# PDN.net
KiCad netlist of a schematic drawn in Altium Designer
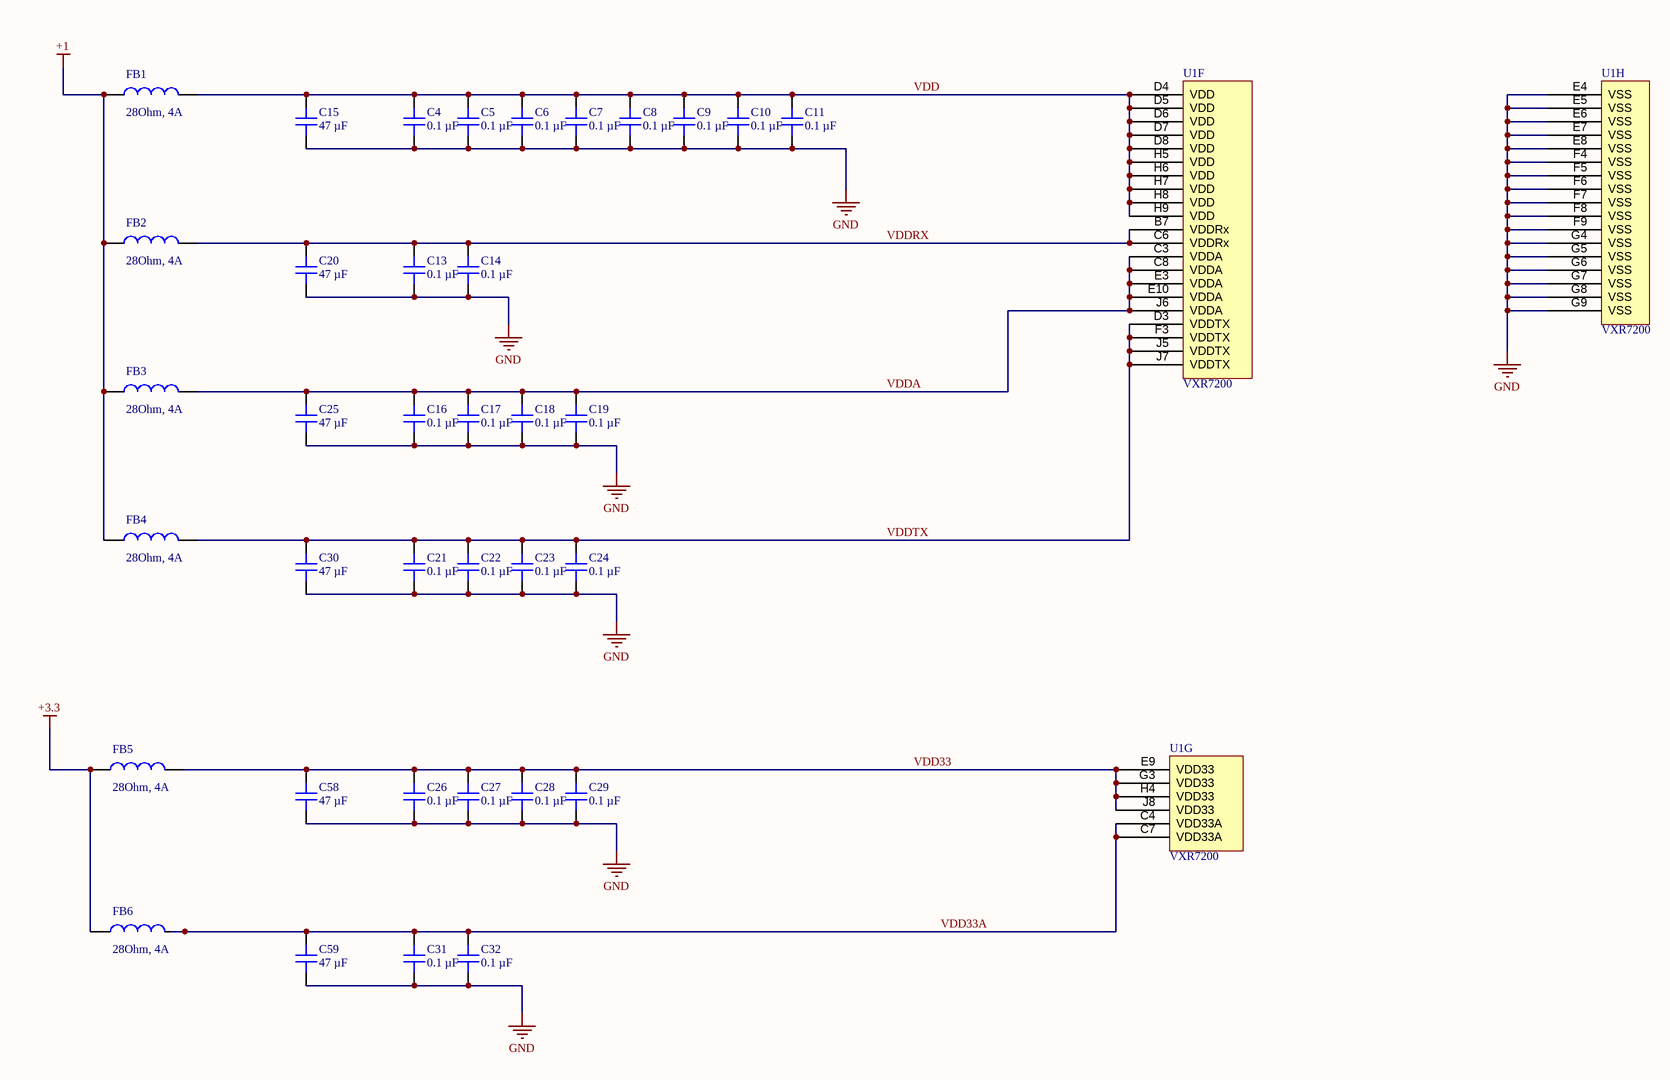
[diagram p0: PDN.SchDoc]

(export (version "E")
  (design (tool "Eeschema 10.0.6"))
  (components
    (comp (ref "C4")
      (value "0.1 µF")
      (footprint "CAP 0201_0603")
      (description "CAP CER 0.1UF 25V X5R 0201")
      (fields
        (field (name "PART NUMBER") "GRM033R61E104KE14D")
        (field (name "MANUFACTURER") "Murata Electronics")
      )
      (libsource (lib "Celestial Altium Library - altium_library") (part "Capacitor"))
    )
    (comp (ref "C5")
      (value "0.1 µF")
      (footprint "CAP 0201_0603")
      (description "CAP CER 0.1UF 25V X5R 0201")
      (fields
        (field (name "PART NUMBER") "GRM033R61E104KE14D")
        (field (name "MANUFACTURER") "Murata Electronics")
      )
      (libsource (lib "Celestial Altium Library - altium_library") (part "Capacitor"))
    )
    (comp (ref "C6")
      (value "0.1 µF")
      (footprint "CAP 0201_0603")
      (description "CAP CER 0.1UF 25V X5R 0201")
      (fields
        (field (name "PART NUMBER") "GRM033R61E104KE14D")
        (field (name "MANUFACTURER") "Murata Electronics")
      )
      (libsource (lib "Celestial Altium Library - altium_library") (part "Capacitor"))
    )
    (comp (ref "C7")
      (value "0.1 µF")
      (footprint "CAP 0201_0603")
      (description "CAP CER 0.1UF 25V X5R 0201")
      (fields
        (field (name "PART NUMBER") "GRM033R61E104KE14D")
        (field (name "MANUFACTURER") "Murata Electronics")
      )
      (libsource (lib "Celestial Altium Library - altium_library") (part "Capacitor"))
    )
    (comp (ref "C8")
      (value "0.1 µF")
      (footprint "CAP 0201_0603")
      (description "CAP CER 0.1UF 25V X5R 0201")
      (fields
        (field (name "PART NUMBER") "GRM033R61E104KE14D")
        (field (name "MANUFACTURER") "Murata Electronics")
      )
      (libsource (lib "Celestial Altium Library - altium_library") (part "Capacitor"))
    )
    (comp (ref "C9")
      (value "0.1 µF")
      (footprint "CAP 0201_0603")
      (description "CAP CER 0.1UF 25V X5R 0201")
      (fields
        (field (name "PART NUMBER") "GRM033R61E104KE14D")
        (field (name "MANUFACTURER") "Murata Electronics")
      )
      (libsource (lib "Celestial Altium Library - altium_library") (part "Capacitor"))
    )
    (comp (ref "C10")
      (value "0.1 µF")
      (footprint "CAP 0201_0603")
      (description "CAP CER 0.1UF 25V X5R 0201")
      (fields
        (field (name "PART NUMBER") "GRM033R61E104KE14D")
        (field (name "MANUFACTURER") "Murata Electronics")
      )
      (libsource (lib "Celestial Altium Library - altium_library") (part "Capacitor"))
    )
    (comp (ref "C11")
      (value "0.1 µF")
      (footprint "CAP 0201_0603")
      (description "CAP CER 0.1UF 25V X5R 0201")
      (fields
        (field (name "PART NUMBER") "GRM033R61E104KE14D")
        (field (name "MANUFACTURER") "Murata Electronics")
      )
      (libsource (lib "Celestial Altium Library - altium_library") (part "Capacitor"))
    )
    (comp (ref "C13")
      (value "0.1 µF")
      (footprint "CAP 0201_0603")
      (description "CAP CER 0.1UF 25V X5R 0201")
      (fields
        (field (name "PART NUMBER") "GRM033R61E104KE14D")
        (field (name "MANUFACTURER") "Murata Electronics")
      )
      (libsource (lib "Celestial Altium Library - altium_library") (part "Capacitor"))
    )
    (comp (ref "C14")
      (value "0.1 µF")
      (footprint "CAP 0201_0603")
      (description "CAP CER 0.1UF 25V X5R 0201")
      (fields
        (field (name "PART NUMBER") "GRM033R61E104KE14D")
        (field (name "MANUFACTURER") "Murata Electronics")
      )
      (libsource (lib "Celestial Altium Library - altium_library") (part "Capacitor"))
    )
    (comp (ref "C15")
      (value "47 µF")
      (footprint "CAP 0603_1608")
      (description "CAP CER 47UF 6.3V X5R 0603")
      (fields
        (field (name "PART NUMBER") "GRM188R60J476ME01D")
        (field (name "MANUFACTURER") "Murata Electronics")
      )
      (libsource (lib "Celestial Altium Library - altium_library") (part "Capacitor"))
    )
    (comp (ref "C16")
      (value "0.1 µF")
      (footprint "CAP 0201_0603")
      (description "CAP CER 0.1UF 25V X5R 0201")
      (fields
        (field (name "PART NUMBER") "GRM033R61E104KE14D")
        (field (name "MANUFACTURER") "Murata Electronics")
      )
      (libsource (lib "Celestial Altium Library - altium_library") (part "Capacitor"))
    )
    (comp (ref "C17")
      (value "0.1 µF")
      (footprint "CAP 0201_0603")
      (description "CAP CER 0.1UF 25V X5R 0201")
      (fields
        (field (name "PART NUMBER") "GRM033R61E104KE14D")
        (field (name "MANUFACTURER") "Murata Electronics")
      )
      (libsource (lib "Celestial Altium Library - altium_library") (part "Capacitor"))
    )
    (comp (ref "C18")
      (value "0.1 µF")
      (footprint "CAP 0201_0603")
      (description "CAP CER 0.1UF 25V X5R 0201")
      (fields
        (field (name "PART NUMBER") "GRM033R61E104KE14D")
        (field (name "MANUFACTURER") "Murata Electronics")
      )
      (libsource (lib "Celestial Altium Library - altium_library") (part "Capacitor"))
    )
    (comp (ref "C19")
      (value "0.1 µF")
      (footprint "CAP 0201_0603")
      (description "CAP CER 0.1UF 25V X5R 0201")
      (fields
        (field (name "PART NUMBER") "GRM033R61E104KE14D")
        (field (name "MANUFACTURER") "Murata Electronics")
      )
      (libsource (lib "Celestial Altium Library - altium_library") (part "Capacitor"))
    )
    (comp (ref "C20")
      (value "47 µF")
      (footprint "CAP 0603_1608")
      (description "CAP CER 47UF 6.3V X5R 0603")
      (fields
        (field (name "PART NUMBER") "GRM188R60J476ME01D")
        (field (name "MANUFACTURER") "Murata Electronics")
      )
      (libsource (lib "Celestial Altium Library - altium_library") (part "Capacitor"))
    )
    (comp (ref "C21")
      (value "0.1 µF")
      (footprint "CAP 0201_0603")
      (description "CAP CER 0.1UF 25V X5R 0201")
      (fields
        (field (name "PART NUMBER") "GRM033R61E104KE14D")
        (field (name "MANUFACTURER") "Murata Electronics")
      )
      (libsource (lib "Celestial Altium Library - altium_library") (part "Capacitor"))
    )
    (comp (ref "C22")
      (value "0.1 µF")
      (footprint "CAP 0201_0603")
      (description "CAP CER 0.1UF 25V X5R 0201")
      (fields
        (field (name "PART NUMBER") "GRM033R61E104KE14D")
        (field (name "MANUFACTURER") "Murata Electronics")
      )
      (libsource (lib "Celestial Altium Library - altium_library") (part "Capacitor"))
    )
    (comp (ref "C23")
      (value "0.1 µF")
      (footprint "CAP 0201_0603")
      (description "CAP CER 0.1UF 25V X5R 0201")
      (fields
        (field (name "PART NUMBER") "GRM033R61E104KE14D")
        (field (name "MANUFACTURER") "Murata Electronics")
      )
      (libsource (lib "Celestial Altium Library - altium_library") (part "Capacitor"))
    )
    (comp (ref "C24")
      (value "0.1 µF")
      (footprint "CAP 0201_0603")
      (description "CAP CER 0.1UF 25V X5R 0201")
      (fields
        (field (name "PART NUMBER") "GRM033R61E104KE14D")
        (field (name "MANUFACTURER") "Murata Electronics")
      )
      (libsource (lib "Celestial Altium Library - altium_library") (part "Capacitor"))
    )
    (comp (ref "C25")
      (value "47 µF")
      (footprint "CAP 0603_1608")
      (description "CAP CER 47UF 6.3V X5R 0603")
      (fields
        (field (name "PART NUMBER") "GRM188R60J476ME01D")
        (field (name "MANUFACTURER") "Murata Electronics")
      )
      (libsource (lib "Celestial Altium Library - altium_library") (part "Capacitor"))
    )
    (comp (ref "C26")
      (value "0.1 µF")
      (footprint "CAP 0201_0603")
      (description "CAP CER 0.1UF 25V X5R 0201")
      (fields
        (field (name "PART NUMBER") "GRM033R61E104KE14D")
        (field (name "MANUFACTURER") "Murata Electronics")
      )
      (libsource (lib "Celestial Altium Library - altium_library") (part "Capacitor"))
    )
    (comp (ref "C27")
      (value "0.1 µF")
      (footprint "CAP 0201_0603")
      (description "CAP CER 0.1UF 25V X5R 0201")
      (fields
        (field (name "PART NUMBER") "GRM033R61E104KE14D")
        (field (name "MANUFACTURER") "Murata Electronics")
      )
      (libsource (lib "Celestial Altium Library - altium_library") (part "Capacitor"))
    )
    (comp (ref "C28")
      (value "0.1 µF")
      (footprint "CAP 0201_0603")
      (description "CAP CER 0.1UF 25V X5R 0201")
      (fields
        (field (name "PART NUMBER") "GRM033R61E104KE14D")
        (field (name "MANUFACTURER") "Murata Electronics")
      )
      (libsource (lib "Celestial Altium Library - altium_library") (part "Capacitor"))
    )
    (comp (ref "C29")
      (value "0.1 µF")
      (footprint "CAP 0201_0603")
      (description "CAP CER 0.1UF 25V X5R 0201")
      (fields
        (field (name "PART NUMBER") "GRM033R61E104KE14D")
        (field (name "MANUFACTURER") "Murata Electronics")
      )
      (libsource (lib "Celestial Altium Library - altium_library") (part "Capacitor"))
    )
    (comp (ref "C30")
      (value "47 µF")
      (footprint "CAP 0603_1608")
      (description "CAP CER 47UF 6.3V X5R 0603")
      (fields
        (field (name "PART NUMBER") "GRM188R60J476ME01D")
        (field (name "MANUFACTURER") "Murata Electronics")
      )
      (libsource (lib "Celestial Altium Library - altium_library") (part "Capacitor"))
    )
    (comp (ref "C31")
      (value "0.1 µF")
      (footprint "CAP 0201_0603")
      (description "CAP CER 0.1UF 25V X5R 0201")
      (fields
        (field (name "PART NUMBER") "GRM033R61E104KE14D")
        (field (name "MANUFACTURER") "Murata Electronics")
      )
      (libsource (lib "Celestial Altium Library - altium_library") (part "Capacitor"))
    )
    (comp (ref "C32")
      (value "0.1 µF")
      (footprint "CAP 0201_0603")
      (description "CAP CER 0.1UF 25V X5R 0201")
      (fields
        (field (name "PART NUMBER") "GRM033R61E104KE14D")
        (field (name "MANUFACTURER") "Murata Electronics")
      )
      (libsource (lib "Celestial Altium Library - altium_library") (part "Capacitor"))
    )
    (comp (ref "C58")
      (value "47 µF")
      (footprint "CAP 0603_1608")
      (description "CAP CER 47UF 6.3V X5R 0603")
      (fields
        (field (name "PART NUMBER") "GRM188R60J476ME01D")
        (field (name "MANUFACTURER") "Murata Electronics")
      )
      (libsource (lib "Celestial Altium Library - altium_library") (part "Capacitor"))
    )
    (comp (ref "C59")
      (value "47 µF")
      (footprint "CAP 0603_1608")
      (description "CAP CER 47UF 6.3V X5R 0603")
      (fields
        (field (name "PART NUMBER") "GRM188R60J476ME01D")
        (field (name "MANUFACTURER") "Murata Electronics")
      )
      (libsource (lib "Celestial Altium Library - altium_library") (part "Capacitor"))
    )
    (comp (ref "FB1")
      (value "28Ohm, 4A")
      (footprint "WE-CBF_0603_High Current")
      (description "WE-CBF SMT EMI Suppression Ferrite Bead, size 0603, 28Ohm, 4A")
      (fields
        (field (name "MANUFACTURER") "Wurth Elektronik")
        (field (name "MANUFACTURER PART NUMBER") "742792603")
      )
      (libsource (lib "WE-CBF (rev22a)") (part "742792603"))
    )
    (comp (ref "FB2")
      (value "28Ohm, 4A")
      (footprint "WE-CBF_0603_High Current")
      (description "WE-CBF SMT EMI Suppression Ferrite Bead, size 0603, 28Ohm, 4A")
      (fields
        (field (name "MANUFACTURER") "Wurth Elektronik")
        (field (name "MANUFACTURER PART NUMBER") "742792603")
      )
      (libsource (lib "WE-CBF (rev22a)") (part "742792603"))
    )
    (comp (ref "FB3")
      (value "28Ohm, 4A")
      (footprint "WE-CBF_0603_High Current")
      (description "WE-CBF SMT EMI Suppression Ferrite Bead, size 0603, 28Ohm, 4A")
      (fields
        (field (name "MANUFACTURER") "Wurth Elektronik")
        (field (name "MANUFACTURER PART NUMBER") "742792603")
      )
      (libsource (lib "WE-CBF (rev22a)") (part "742792603"))
    )
    (comp (ref "FB4")
      (value "28Ohm, 4A")
      (footprint "WE-CBF_0603_High Current")
      (description "WE-CBF SMT EMI Suppression Ferrite Bead, size 0603, 28Ohm, 4A")
      (fields
        (field (name "MANUFACTURER") "Wurth Elektronik")
        (field (name "MANUFACTURER PART NUMBER") "742792603")
      )
      (libsource (lib "WE-CBF (rev22a)") (part "742792603"))
    )
    (comp (ref "FB5")
      (value "28Ohm, 4A")
      (footprint "WE-CBF_0603_High Current")
      (description "WE-CBF SMT EMI Suppression Ferrite Bead, size 0603, 28Ohm, 4A")
      (fields
        (field (name "MANUFACTURER") "Wurth Elektronik")
        (field (name "MANUFACTURER PART NUMBER") "742792603")
      )
      (libsource (lib "WE-CBF (rev22a)") (part "742792603"))
    )
    (comp (ref "FB6")
      (value "28Ohm, 4A")
      (footprint "WE-CBF_0603_High Current")
      (description "WE-CBF SMT EMI Suppression Ferrite Bead, size 0603, 28Ohm, 4A")
      (fields
        (field (name "MANUFACTURER") "Wurth Elektronik")
        (field (name "MANUFACTURER PART NUMBER") "742792603")
      )
      (libsource (lib "WE-CBF (rev22a)") (part "742792603"))
    )
    (comp (ref "U1")
      (value "VXR7200")
      (footprint "BGA100P9X9-81A")
      (description "VXR7200 DP to MIPI-DSI bridge")
      (libsource (lib "SimulaVR") (part "VXR7200-Symbol-1"))
    )
  )
  (nets
    (net (code "1") (name "+1") (class "Default")
      (node (ref "FB1") (pin "1") (pinfunction "1_1") (pintype "passive"))
      (node (ref "FB2") (pin "1") (pinfunction "1_1") (pintype "passive"))
      (node (ref "FB3") (pin "1") (pinfunction "1_1") (pintype "passive"))
      (node (ref "FB4") (pin "1") (pinfunction "1_1") (pintype "passive"))
    )
    (net (code "2") (name "+3.3") (class "Default")
      (node (ref "FB5") (pin "1") (pinfunction "1_1") (pintype "passive"))
      (node (ref "FB6") (pin "1") (pinfunction "1_1") (pintype "passive"))
    )
    (net (code "3") (name "/VDD") (class "Default")
      (node (ref "C10") (pin "2") (pinfunction "2_2") (pintype "passive"))
      (node (ref "C11") (pin "2") (pinfunction "2_2") (pintype "passive"))
      (node (ref "C15") (pin "2") (pinfunction "2_2") (pintype "passive"))
      (node (ref "C4") (pin "2") (pinfunction "2_2") (pintype "passive"))
      (node (ref "C5") (pin "2") (pinfunction "2_2") (pintype "passive"))
      (node (ref "C6") (pin "2") (pinfunction "2_2") (pintype "passive"))
      (node (ref "C7") (pin "2") (pinfunction "2_2") (pintype "passive"))
      (node (ref "C8") (pin "2") (pinfunction "2_2") (pintype "passive"))
      (node (ref "C9") (pin "2") (pinfunction "2_2") (pintype "passive"))
      (node (ref "FB1") (pin "2") (pinfunction "2_2") (pintype "passive"))
      (node (ref "U1") (pin "D4") (pinfunction "VDD_D4") (pintype "power_in"))
      (node (ref "U1") (pin "D5") (pinfunction "VDD_D5") (pintype "power_in"))
      (node (ref "U1") (pin "D6") (pinfunction "VDD_D6") (pintype "power_in"))
      (node (ref "U1") (pin "D7") (pinfunction "VDD_D7") (pintype "power_in"))
      (node (ref "U1") (pin "D8") (pinfunction "VDD_D8") (pintype "power_in"))
      (node (ref "U1") (pin "H5") (pinfunction "VDD_H5") (pintype "power_in"))
      (node (ref "U1") (pin "H6") (pinfunction "VDD_H6") (pintype "power_in"))
      (node (ref "U1") (pin "H7") (pinfunction "VDD_H7") (pintype "power_in"))
      (node (ref "U1") (pin "H8") (pinfunction "VDD_H8") (pintype "power_in"))
      (node (ref "U1") (pin "H9") (pinfunction "VDD_H9") (pintype "power_in"))
    )
    (net (code "4") (name "/VDD33") (class "Default")
      (node (ref "C26") (pin "2") (pinfunction "2_2") (pintype "passive"))
      (node (ref "C27") (pin "2") (pinfunction "2_2") (pintype "passive"))
      (node (ref "C28") (pin "2") (pinfunction "2_2") (pintype "passive"))
      (node (ref "C29") (pin "2") (pinfunction "2_2") (pintype "passive"))
      (node (ref "C58") (pin "2") (pinfunction "2_2") (pintype "passive"))
      (node (ref "FB5") (pin "2") (pinfunction "2_2") (pintype "passive"))
      (node (ref "U1") (pin "E9") (pinfunction "VDD33_E9") (pintype "power_in"))
      (node (ref "U1") (pin "G3") (pinfunction "VDD33_G3") (pintype "power_in"))
      (node (ref "U1") (pin "H4") (pinfunction "VDD33_H4") (pintype "power_in"))
      (node (ref "U1") (pin "J8") (pinfunction "VDD33_J8") (pintype "power_in"))
    )
    (net (code "5") (name "/VDD33A") (class "Default")
      (node (ref "C31") (pin "2") (pinfunction "2_2") (pintype "passive"))
      (node (ref "C32") (pin "2") (pinfunction "2_2") (pintype "passive"))
      (node (ref "C59") (pin "2") (pinfunction "2_2") (pintype "passive"))
      (node (ref "FB6") (pin "2") (pinfunction "2_2") (pintype "passive"))
      (node (ref "U1") (pin "C4") (pinfunction "VDD33A_C4") (pintype "power_in"))
      (node (ref "U1") (pin "C7") (pinfunction "VDD33A_C7") (pintype "power_in"))
    )
    (net (code "6") (name "/VDDA") (class "Default")
      (node (ref "C16") (pin "2") (pinfunction "2_2") (pintype "passive"))
      (node (ref "C17") (pin "2") (pinfunction "2_2") (pintype "passive"))
      (node (ref "C18") (pin "2") (pinfunction "2_2") (pintype "passive"))
      (node (ref "C19") (pin "2") (pinfunction "2_2") (pintype "passive"))
      (node (ref "C25") (pin "2") (pinfunction "2_2") (pintype "passive"))
      (node (ref "FB3") (pin "2") (pinfunction "2_2") (pintype "passive"))
      (node (ref "U1") (pin "C3") (pinfunction "VDDA_C3") (pintype "power_in"))
      (node (ref "U1") (pin "C8") (pinfunction "VDDA_C8") (pintype "power_in"))
      (node (ref "U1") (pin "E10") (pinfunction "VDDA_E10") (pintype "power_in"))
      (node (ref "U1") (pin "E3") (pinfunction "VDDA_E3") (pintype "power_in"))
      (node (ref "U1") (pin "J6") (pinfunction "VDDA_J6") (pintype "power_in"))
    )
    (net (code "7") (name "/VDDRX") (class "Default")
      (node (ref "C13") (pin "2") (pinfunction "2_2") (pintype "passive"))
      (node (ref "C14") (pin "2") (pinfunction "2_2") (pintype "passive"))
      (node (ref "C20") (pin "2") (pinfunction "2_2") (pintype "passive"))
      (node (ref "FB2") (pin "2") (pinfunction "2_2") (pintype "passive"))
      (node (ref "U1") (pin "B7") (pinfunction "VDDRx_B7") (pintype "power_in"))
      (node (ref "U1") (pin "C6") (pinfunction "VDDRx_C6") (pintype "power_in"))
    )
    (net (code "8") (name "/VDDTX") (class "Default")
      (node (ref "C21") (pin "2") (pinfunction "2_2") (pintype "passive"))
      (node (ref "C22") (pin "2") (pinfunction "2_2") (pintype "passive"))
      (node (ref "C23") (pin "2") (pinfunction "2_2") (pintype "passive"))
      (node (ref "C24") (pin "2") (pinfunction "2_2") (pintype "passive"))
      (node (ref "C30") (pin "2") (pinfunction "2_2") (pintype "passive"))
      (node (ref "FB4") (pin "2") (pinfunction "2_2") (pintype "passive"))
      (node (ref "U1") (pin "D3") (pinfunction "VDDTX_D3") (pintype "power_in"))
      (node (ref "U1") (pin "F3") (pinfunction "VDDTX_F3") (pintype "power_in"))
      (node (ref "U1") (pin "J5") (pinfunction "VDDTX_J5") (pintype "power_in"))
      (node (ref "U1") (pin "J7") (pinfunction "VDDTX_J7") (pintype "power_in"))
    )
    (net (code "9") (name "GND") (class "Default")
      (node (ref "C10") (pin "1") (pinfunction "1_1") (pintype "passive"))
      (node (ref "C11") (pin "1") (pinfunction "1_1") (pintype "passive"))
      (node (ref "C13") (pin "1") (pinfunction "1_1") (pintype "passive"))
      (node (ref "C14") (pin "1") (pinfunction "1_1") (pintype "passive"))
      (node (ref "C15") (pin "1") (pinfunction "1_1") (pintype "passive"))
      (node (ref "C16") (pin "1") (pinfunction "1_1") (pintype "passive"))
      (node (ref "C17") (pin "1") (pinfunction "1_1") (pintype "passive"))
      (node (ref "C18") (pin "1") (pinfunction "1_1") (pintype "passive"))
      (node (ref "C19") (pin "1") (pinfunction "1_1") (pintype "passive"))
      (node (ref "C20") (pin "1") (pinfunction "1_1") (pintype "passive"))
      (node (ref "C21") (pin "1") (pinfunction "1_1") (pintype "passive"))
      (node (ref "C22") (pin "1") (pinfunction "1_1") (pintype "passive"))
      (node (ref "C23") (pin "1") (pinfunction "1_1") (pintype "passive"))
      (node (ref "C24") (pin "1") (pinfunction "1_1") (pintype "passive"))
      (node (ref "C25") (pin "1") (pinfunction "1_1") (pintype "passive"))
      (node (ref "C26") (pin "1") (pinfunction "1_1") (pintype "passive"))
      (node (ref "C27") (pin "1") (pinfunction "1_1") (pintype "passive"))
      (node (ref "C28") (pin "1") (pinfunction "1_1") (pintype "passive"))
      (node (ref "C29") (pin "1") (pinfunction "1_1") (pintype "passive"))
      (node (ref "C30") (pin "1") (pinfunction "1_1") (pintype "passive"))
      (node (ref "C31") (pin "1") (pinfunction "1_1") (pintype "passive"))
      (node (ref "C32") (pin "1") (pinfunction "1_1") (pintype "passive"))
      (node (ref "C4") (pin "1") (pinfunction "1_1") (pintype "passive"))
      (node (ref "C5") (pin "1") (pinfunction "1_1") (pintype "passive"))
      (node (ref "C58") (pin "1") (pinfunction "1_1") (pintype "passive"))
      (node (ref "C59") (pin "1") (pinfunction "1_1") (pintype "passive"))
      (node (ref "C6") (pin "1") (pinfunction "1_1") (pintype "passive"))
      (node (ref "C7") (pin "1") (pinfunction "1_1") (pintype "passive"))
      (node (ref "C8") (pin "1") (pinfunction "1_1") (pintype "passive"))
      (node (ref "C9") (pin "1") (pinfunction "1_1") (pintype "passive"))
      (node (ref "U1") (pin "E4") (pinfunction "VSS_E4") (pintype "power_in"))
      (node (ref "U1") (pin "E5") (pinfunction "VSS_E5") (pintype "power_in"))
      (node (ref "U1") (pin "E6") (pinfunction "VSS_E6") (pintype "power_in"))
      (node (ref "U1") (pin "E7") (pinfunction "VSS_E7") (pintype "power_in"))
      (node (ref "U1") (pin "E8") (pinfunction "VSS_E8") (pintype "power_in"))
      (node (ref "U1") (pin "F4") (pinfunction "VSS_F4") (pintype "power_in"))
      (node (ref "U1") (pin "F5") (pinfunction "VSS_F5") (pintype "power_in"))
      (node (ref "U1") (pin "F6") (pinfunction "VSS_F6") (pintype "power_in"))
      (node (ref "U1") (pin "F7") (pinfunction "VSS_F7") (pintype "power_in"))
      (node (ref "U1") (pin "F8") (pinfunction "VSS_F8") (pintype "power_in"))
      (node (ref "U1") (pin "F9") (pinfunction "VSS_F9") (pintype "power_in"))
      (node (ref "U1") (pin "G4") (pinfunction "VSS_G4") (pintype "power_in"))
      (node (ref "U1") (pin "G5") (pinfunction "VSS_G5") (pintype "power_in"))
      (node (ref "U1") (pin "G6") (pinfunction "VSS_G6") (pintype "power_in"))
      (node (ref "U1") (pin "G7") (pinfunction "VSS_G7") (pintype "power_in"))
      (node (ref "U1") (pin "G8") (pinfunction "VSS_G8") (pintype "power_in"))
      (node (ref "U1") (pin "G9") (pinfunction "VSS_G9") (pintype "power_in"))
    )
  )
)
